# Mobo.net
KiCad netlist of a schematic drawn in Altium Designer
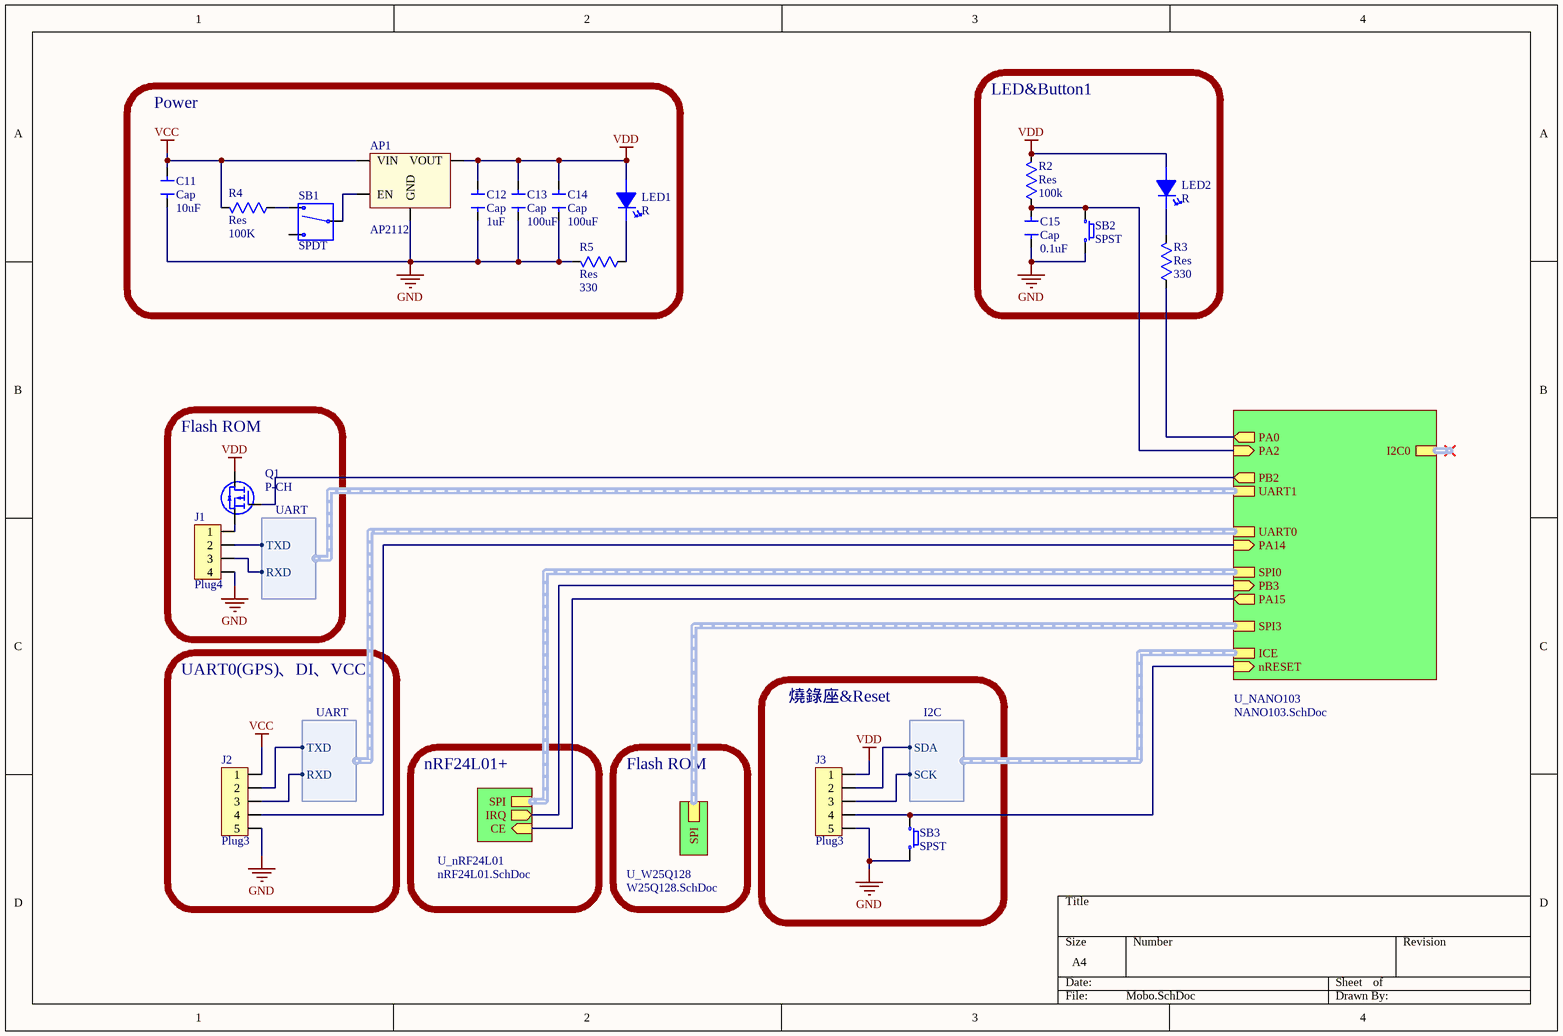
[diagram p0: Mobo.SchDoc]

(export (version "E")
  (design (tool "Eeschema 10.0.6"))
  (components
    (comp (ref "AP1") (value "AP2112") (footprint "SOT-23-5") (libsource (lib "ZGR") (part "AP2112")))
    (comp (ref "C11")
      (value "Cap")
      (footprint "Cap_0603")
      (fields (field (name "ALTIUM_VALUE") "10uF"))
      (libsource (lib "ZGR") (part "Cap"))
    )
    (comp (ref "C12")
      (value "Cap")
      (footprint "Cap_0603")
      (fields (field (name "ALTIUM_VALUE") "1uF"))
      (libsource (lib "ZGR") (part "Cap"))
    )
    (comp (ref "C13")
      (value "Cap")
      (footprint "CAP_1206")
      (fields (field (name "ALTIUM_VALUE") "100uF"))
      (libsource (lib "ZGR") (part "Cap"))
    )
    (comp (ref "C14")
      (value "Cap")
      (footprint "CAP_1206")
      (fields (field (name "ALTIUM_VALUE") "100uF"))
      (libsource (lib "ZGR") (part "Cap"))
    )
    (comp (ref "C15")
      (value "Cap")
      (footprint "Cap_0603")
      (fields (field (name "ALTIUM_VALUE") "0.1uF"))
      (libsource (lib "ZGR") (part "Cap"))
    )
    (comp (ref "J1") (value "Plug4") (footprint "JST_2.0mm_4pin_180") (libsource (lib "ZGR") (part "Plug4")))
    (comp (ref "J2") (value "Plug3") (footprint "GH_1.25mm_Thru_5pin") (libsource (lib "ZGR") (part "Plug5")))
    (comp (ref "J3") (value "Plug3") (footprint "GH_1.25mm_Thru_5pin") (libsource (lib "ZGR") (part "Plug5")))
    (comp (ref "LED1") (value "R") (footprint "SMD-0603_LED") (libsource (lib "ZGR") (part "LED")))
    (comp (ref "LED2") (value "R") (footprint "SMD-0603_LED") (libsource (lib "ZGR") (part "LED")))
    (comp (ref "Q1")
      (value "SI2301DS-T1")
      (footprint "SOT-23")
      (description "Trans MOSFET P-CH 20V 2.3A 3-Pin TO-236 T/R")
      (fields (field (name "MANUFACTURER") "Vishay Siliconix") (field (name "POLARITY") "P-CH"))
      (libsource (lib "ZGR") (part "SI2301DS-T1"))
    )
    (comp (ref "R2")
      (value "Res")
      (footprint "RES_0603")
      (fields (field (name "ALTIUM_VALUE") "100k"))
      (libsource (lib "ZGR") (part "Res"))
    )
    (comp (ref "R3")
      (value "Res")
      (footprint "RES_0603")
      (fields (field (name "ALTIUM_VALUE") "330"))
      (libsource (lib "ZGR") (part "Res"))
    )
    (comp (ref "R4")
      (value "Res")
      (footprint "RES_0603")
      (fields (field (name "ALTIUM_VALUE") "100K"))
      (libsource (lib "ZGR") (part "Res"))
    )
    (comp (ref "R5")
      (value "Res")
      (footprint "RES_0603")
      (fields (field (name "ALTIUM_VALUE") "330"))
      (libsource (lib "ZGR") (part "Res"))
    )
    (comp (ref "SB1") (value "SPDT") (footprint "SS-SK-02P") (libsource (lib "ZGR") (part "Switch_Button2")))
    (comp (ref "SB2")
      (value "SPST")
      (footprint "TACK-SW_SMD 2P 4x3mm_2")
      (libsource (lib "ZGR") (part "Switch_Button1"))
    )
    (comp (ref "SB3")
      (value "SPST")
      (footprint "TACK-SW_SMD 2P 4x3mm_2")
      (libsource (lib "ZGR") (part "Switch_Button1"))
    )
  )
  (nets
    (net (code "5") (name "/PA0") (class "Default")
      (node (ref "R3") (pin "2") (pinfunction "2_2") (pintype "passive"))
    )
    (net (code "6") (name "/PA2") (class "Default")
      (node (ref "C15") (pin "2") (pinfunction "2_2") (pintype "passive"))
      (node (ref "R2") (pin "2") (pinfunction "2_2") (pintype "passive"))
      (node (ref "SB2") (pin "2") (pinfunction "2_2") (pintype "passive"))
    )
    (net (code "7") (name "/PA14") (class "Default")
      (node (ref "J2") (pin "4") (pinfunction "4_4") (pintype "passive"))
    )
    (net (code "9") (name "/PB2") (class "Default")
      (node (ref "Q1") (pin "2") (pinfunction "2_2") (pintype "passive"))
    )
    (net (code "10") (name "/SCK") (class "Default")
      (node (ref "J3") (pin "3") (pinfunction "3_3") (pintype "passive"))
    )
    (net (code "11") (name "/SDA") (class "Default")
      (node (ref "J3") (pin "2") (pinfunction "2_2") (pintype "passive"))
    )
    (net (code "14") (name "/nRESET") (class "Default")
      (node (ref "J3") (pin "4") (pinfunction "4_4") (pintype "passive"))
      (node (ref "SB3") (pin "1") (pinfunction "1_1") (pintype "passive"))
    )
    (net (code "17") (name "GND") (class "Default")
      (node (ref "AP1") (pin "2") (pinfunction "GND_2") (pintype "passive"))
      (node (ref "C11") (pin "2") (pinfunction "2_2") (pintype "passive"))
      (node (ref "C12") (pin "2") (pinfunction "2_2") (pintype "passive"))
      (node (ref "C13") (pin "2") (pinfunction "2_2") (pintype "passive"))
      (node (ref "C14") (pin "2") (pinfunction "2_2") (pintype "passive"))
      (node (ref "C15") (pin "1") (pinfunction "1_1") (pintype "passive"))
      (node (ref "J1") (pin "4") (pinfunction "4_4") (pintype "passive"))
      (node (ref "J2") (pin "5") (pinfunction "5_5") (pintype "passive"))
      (node (ref "J3") (pin "5") (pinfunction "5_5") (pintype "passive"))
      (node (ref "R5") (pin "1") (pinfunction "1_1") (pintype "passive"))
      (node (ref "SB2") (pin "1") (pinfunction "1_1") (pintype "passive"))
      (node (ref "SB3") (pin "2") (pinfunction "2_2") (pintype "passive"))
    )
    (net (code "18") (name "Net-(AP1-EN)") (class "Default")
      (node (ref "AP1") (pin "3") (pinfunction "EN_3") (pintype "passive"))
      (node (ref "SB1") (pin "2") (pinfunction "2_2") (pintype "passive"))
    )
    (net (code "19") (name "Net-(J1-Pad1)") (class "Default")
      (node (ref "J1") (pin "1") (pinfunction "1_1") (pintype "passive"))
      (node (ref "Q1") (pin "3") (pinfunction "3_3") (pintype "passive"))
    )
    (net (code "20") (name "Net-(LED1-Pad2)") (class "Default")
      (node (ref "LED1") (pin "2") (pinfunction "2_2") (pintype "passive"))
      (node (ref "R5") (pin "2") (pinfunction "2_2") (pintype "passive"))
    )
    (net (code "21") (name "Net-(LED2-Pad2)") (class "Default")
      (node (ref "LED2") (pin "2") (pinfunction "2_2") (pintype "passive"))
      (node (ref "R3") (pin "1") (pinfunction "1_1") (pintype "passive"))
    )
    (net (code "22") (name "Net-(R4-Pad2)") (class "Default")
      (node (ref "R4") (pin "2") (pinfunction "2_2") (pintype "passive"))
      (node (ref "SB1") (pin "3") (pinfunction "3_3") (pintype "passive"))
    )
    (net (code "23") (name "VCC") (class "Default")
      (node (ref "AP1") (pin "1") (pinfunction "VIN_1") (pintype "passive"))
      (node (ref "C11") (pin "1") (pinfunction "1_1") (pintype "passive"))
      (node (ref "J2") (pin "1") (pinfunction "1_1") (pintype "passive"))
      (node (ref "R4") (pin "1") (pinfunction "1_1") (pintype "passive"))
    )
    (net (code "24") (name "VDD") (class "Default")
      (node (ref "AP1") (pin "5") (pinfunction "VOUT_5") (pintype "passive"))
      (node (ref "C12") (pin "1") (pinfunction "1_1") (pintype "passive"))
      (node (ref "C13") (pin "1") (pinfunction "1_1") (pintype "passive"))
      (node (ref "C14") (pin "1") (pinfunction "1_1") (pintype "passive"))
      (node (ref "J3") (pin "1") (pinfunction "1_1") (pintype "passive"))
      (node (ref "LED1") (pin "1") (pinfunction "1_1") (pintype "passive"))
      (node (ref "LED2") (pin "1") (pinfunction "1_1") (pintype "passive"))
      (node (ref "Q1") (pin "1") (pinfunction "1_1") (pintype "passive"))
      (node (ref "R2") (pin "1") (pinfunction "1_1") (pintype "passive"))
    )
    (net (code "25") (name "unconnected-(J1-Pad2)") (class "Default")
      (node (ref "J1") (pin "2") (pinfunction "2_2") (pintype "passive"))
    )
    (net (code "26") (name "unconnected-(J1-Pad3)") (class "Default")
      (node (ref "J1") (pin "3") (pinfunction "3_3") (pintype "passive"))
    )
    (net (code "27") (name "unconnected-(J2-Pad2)") (class "Default")
      (node (ref "J2") (pin "2") (pinfunction "2_2") (pintype "passive"))
    )
    (net (code "28") (name "unconnected-(J2-Pad3)") (class "Default")
      (node (ref "J2") (pin "3") (pinfunction "3_3") (pintype "passive"))
    )
    (net (code "29") (name "unconnected-(SB1-Pad1)") (class "Default")
      (node (ref "SB1") (pin "1") (pinfunction "1_1") (pintype "passive"))
    )
  )
)
